# 13_LIGHT.net
KiCad netlist of a schematic drawn in Altium Designer
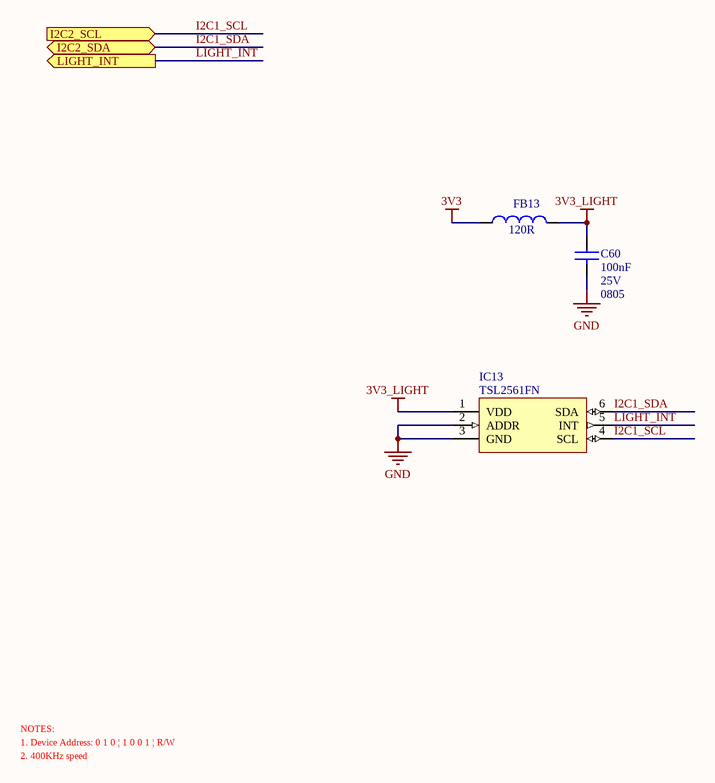
[diagram p0: 13.LIGHT.SchDoc]

(export (version "E")
  (design (tool "Eeschema 10.0.6"))
  (components
    (comp (ref "C60")
      (value "CAP_NP")
      (footprint "CAPC2012X100N_EIA0805")
      (description "CAP CER 0.1UF 25V X7R 0805")
      (fields
        (field (name "PART NUMBER") "SCAP00300093")
        (field (name "CAPACITANCE") "100nF")
        (field (name "TOLERANCE") "±10%")
        (field (name "VOLTAGE - RATED") "25V")
        (field (name "PACKAGE / CASE") "0805")
      )
      (libsource (lib "ComponentDatabase") (part "CAP_NP"))
    )
    (comp (ref "FB13")
      (value "BEAD")
      (footprint "FILC2012X100N_EIA0805")
      (description "FERRITE CHIP POWER 120 OHM SMD")
      (fields
        (field (name "PART NUMBER") "SFIL00005")
        (field (name "IMPEDANCE") "120R")
        (field (name "MANUFACTURER") "Laird-Signal Integrity Products")
      )
      (libsource (lib "ComponentDatabase") (part "BEAD"))
    )
    (comp (ref "IC13")
      (value "TSL256x")
      (footprint "DFN-6")
      (description "IC LIGHT TO DGTL CONV 6-DFN")
      (fields
        (field (name "PART NUMBER") "SSEN00013")
        (field (name "VOLTAGE") "2.7 V ~ 3.6 V")
        (field (name "MANUFACTURER PART NUMBER") "TSL2561FN")
      )
      (libsource (lib "ComponentDatabase") (part "TSL256x"))
    )
  )
  (nets
    (net (code "1") (name "/I2C1_SCL") (class "Default")
      (node (ref "IC13") (pin "4") (pinfunction "SCL_4") (pintype "bidirectional"))
    )
    (net (code "2") (name "/I2C1_SDA") (class "Default")
      (node (ref "IC13") (pin "6") (pinfunction "SDA_6") (pintype "bidirectional"))
    )
    (net (code "3") (name "/LIGHT_INT") (class "Default")
      (node (ref "IC13") (pin "5") (pinfunction "INT_5") (pintype "output"))
    )
    (net (code "4") (name "3V3") (class "Default")
      (node (ref "FB13") (pin "1") (pinfunction "1_1") (pintype "passive"))
    )
    (net (code "5") (name "3V3_LIGHT") (class "Default")
      (node (ref "C60") (pin "1") (pinfunction "1_1") (pintype "passive"))
      (node (ref "FB13") (pin "2") (pinfunction "2_2") (pintype "passive"))
      (node (ref "IC13") (pin "1") (pinfunction "VDD_1") (pintype "power_in"))
    )
    (net (code "6") (name "GND") (class "Default")
      (node (ref "C60") (pin "2") (pinfunction "2_2") (pintype "passive"))
      (node (ref "IC13") (pin "2") (pinfunction "ADDR_2") (pintype "input"))
      (node (ref "IC13") (pin "3") (pinfunction "GND_3") (pintype "power_in"))
    )
  )
)
